# OPA541.net
KiCad netlist of a schematic drawn in EasyEDA Pro
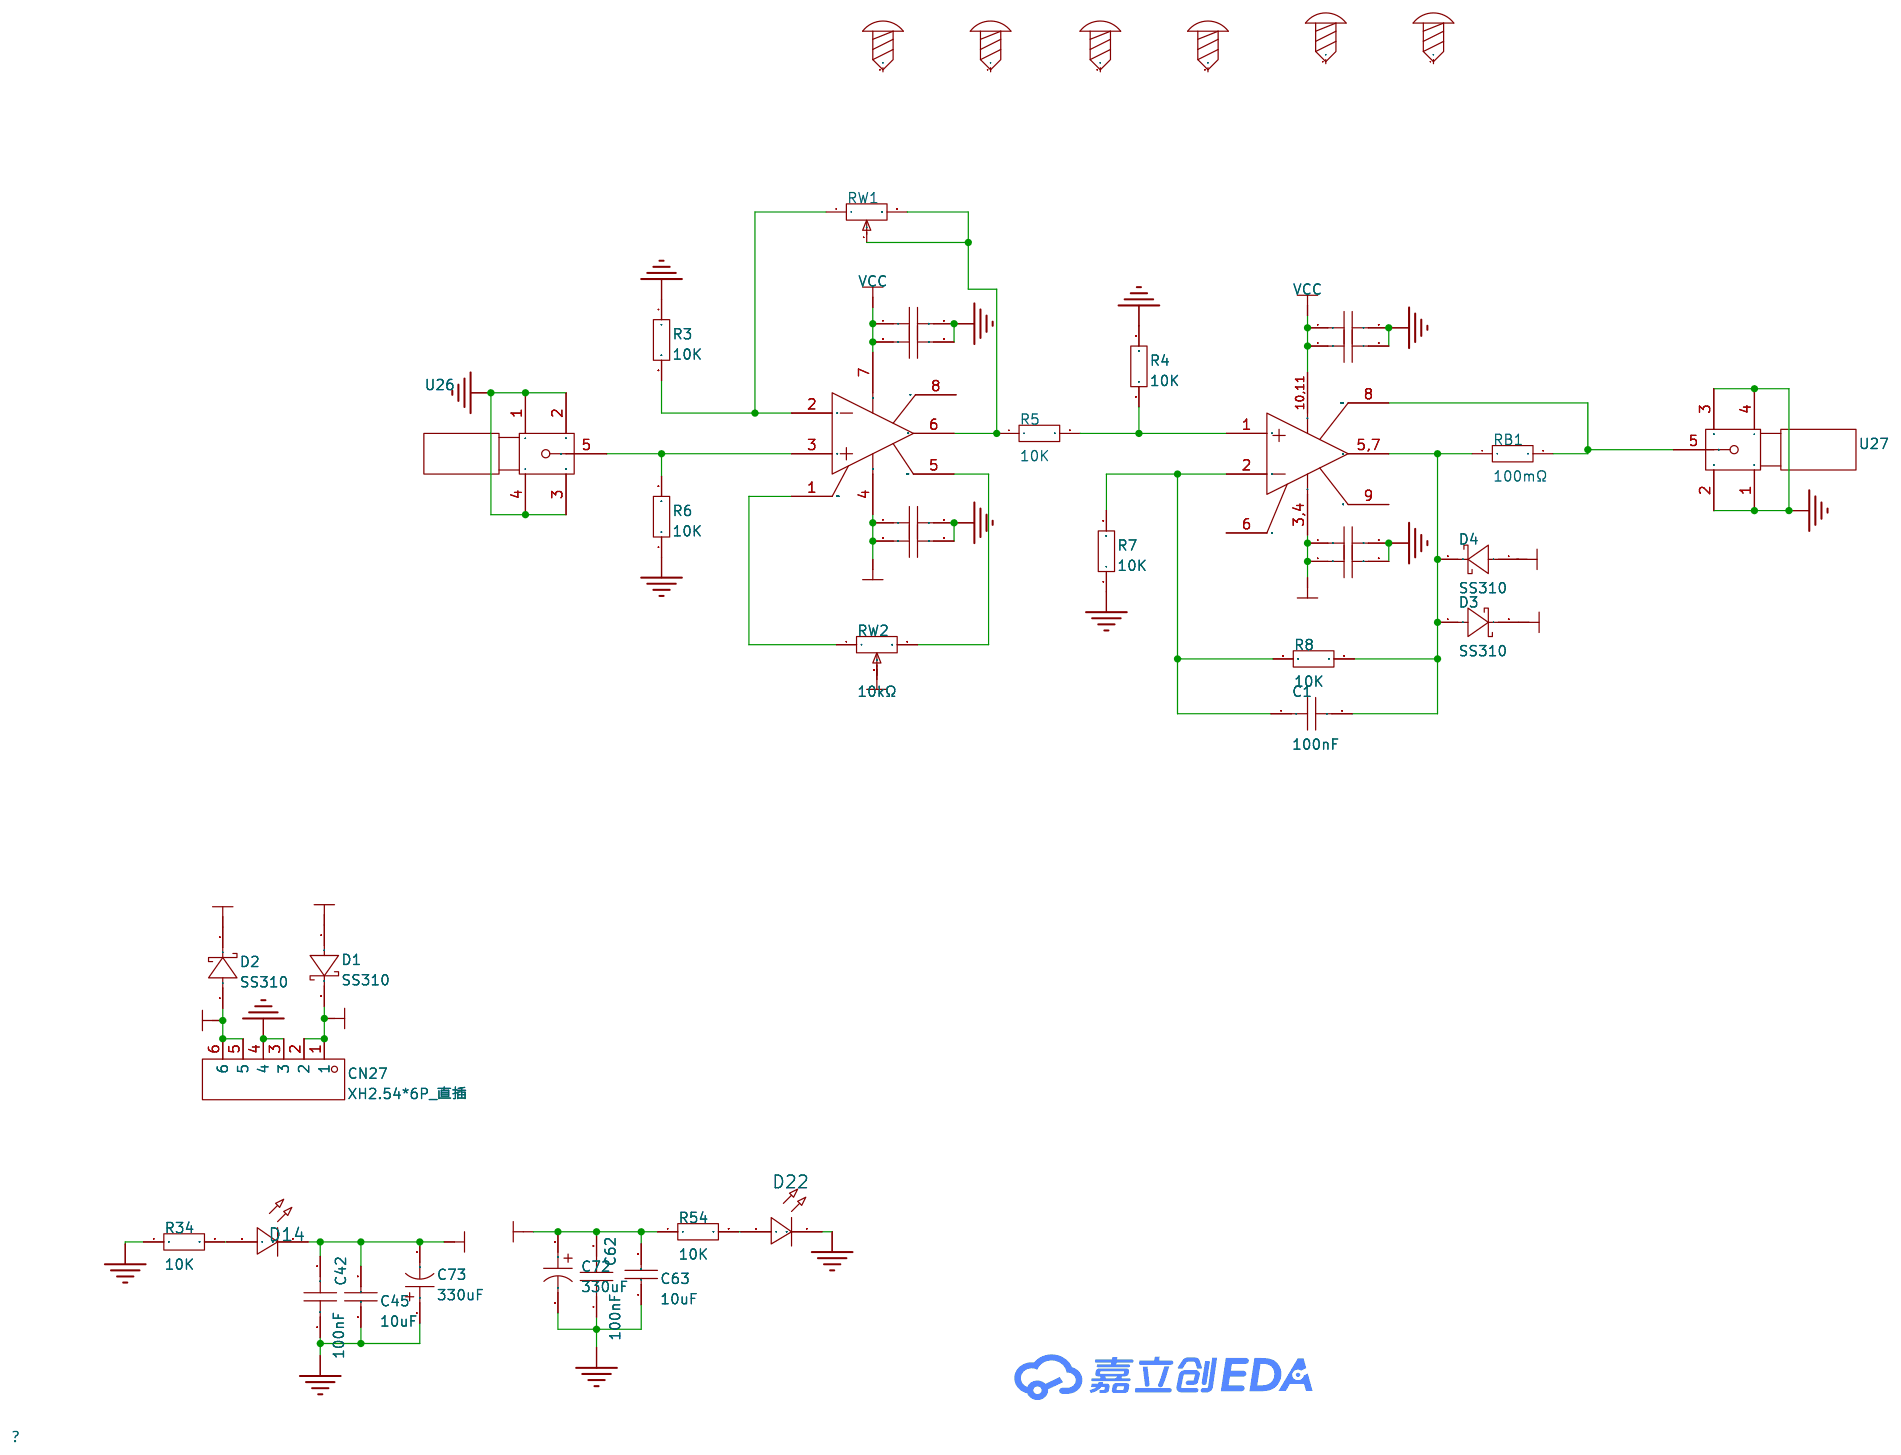
[diagram p0: schematic sheet]

(export (version "E")
  (design (tool "Eeschema 10.0.6"))
  (components
    (comp (ref "C1")
      (value "100nF")
      (footprint "easyedapro:C0805")
      (libsource (lib "easyedapro") (part "CapAcitance"))
    )
    (comp (ref "C42")
      (value "100nF")
      (footprint "easyedapro:C0805")
      (libsource (lib "easyedapro") (part "CapAcitance"))
    )
    (comp (ref "C45")
      (value "10uF")
      (footprint "easyedapro:C1210")
      (description "容值:10uF;精度:±10%;额定电压:25V;材质(温度系数):X7R;")
      (fields
        (field (name "Manufacturer Part") "CL32B106KAJNNNE")
        (field (name "Manufacturer") "SAMSUNG(三星)")
      )
      (libsource (lib "easyedapro") (part "CL32B106KAJNNNE"))
    )
    (comp (ref "C62")
      (value "100nF")
      (footprint "easyedapro:C0805")
      (libsource (lib "easyedapro") (part "CapAcitance"))
    )
    (comp (ref "C63")
      (value "10uF")
      (footprint "easyedapro:C1210")
      (description "容值:10uF;精度:±10%;额定电压:25V;材质(温度系数):X7R;")
      (fields
        (field (name "Manufacturer Part") "CL32B106KAJNNNE")
        (field (name "Manufacturer") "SAMSUNG(三星)")
      )
      (libsource (lib "easyedapro") (part "CL32B106KAJNNNE"))
    )
    (comp (ref "C64")
      (value "100nF")
      (footprint "easyedapro:C0805")
      (libsource (lib "easyedapro") (part "CapAcitance"))
    )
    (comp (ref "C65")
      (value "100nF")
      (footprint "easyedapro:C0805")
      (libsource (lib "easyedapro") (part "CapAcitance"))
    )
    (comp (ref "C66")
      (value "100nF")
      (footprint "easyedapro:C0805")
      (libsource (lib "easyedapro") (part "CapAcitance"))
    )
    (comp (ref "C67")
      (value "100nF")
      (footprint "easyedapro:C0805")
      (libsource (lib "easyedapro") (part "CapAcitance"))
    )
    (comp (ref "C68")
      (value "100nF")
      (footprint "easyedapro:C0805")
      (libsource (lib "easyedapro") (part "CapAcitance"))
    )
    (comp (ref "C69")
      (value "100nF")
      (footprint "easyedapro:C0805")
      (libsource (lib "easyedapro") (part "CapAcitance"))
    )
    (comp (ref "C70")
      (value "100nF")
      (footprint "easyedapro:C0805")
      (libsource (lib "easyedapro") (part "CapAcitance"))
    )
    (comp (ref "C71")
      (value "100nF")
      (footprint "easyedapro:C0805")
      (libsource (lib "easyedapro") (part "CapAcitance"))
    )
    (comp (ref "C72")
      (value "330uF")
      (footprint "easyedapro:CAP-SMD_BD10.0-L10.3-W10.3-LS11.0-FD-1")
      (description "容值:330uF;精度:±20%;额定电压:50V;纹波电流:285mA@120Hz;")
      (fields (field (name "Manufacturer Part") "CS1H331M-CRG10") (field (name "Manufacturer") "ROQANG(容强)"))
      (libsource (lib "easyedapro") (part "CS1H331M-CRG10"))
    )
    (comp (ref "C73")
      (value "330uF")
      (footprint "easyedapro:CAP-SMD_BD10.0-L10.3-W10.3-LS11.0-FD-1")
      (description "容值:330uF;精度:±20%;额定电压:50V;纹波电流:285mA@120Hz;")
      (fields (field (name "Manufacturer Part") "CS1H331M-CRG10") (field (name "Manufacturer") "ROQANG(容强)"))
      (libsource (lib "easyedapro") (part "CS1H331M-CRG10"))
    )
    (comp (ref "CN27")
      (value "XH2.54*6P_直插")
      (footprint "easyedapro:CONN-TH_XH2.54-6P")
      (libsource (lib "easyedapro") (part "XH2.54*6P_直插"))
    )
    (comp (ref "D1")
      (value "SS310")
      (footprint "easyedapro:SMA_L4.3-W2.6-LS5.0-FD")
      (description "二极管配置:独立式;正向压降(Vf):850mV@3A;直流反向耐压(Vr):100V;整流电流:3A;")
      (fields (field (name "Manufacturer") "宏迦橙"))
      (libsource (lib "easyedapro") (part "SS310_C7420364"))
    )
    (comp (ref "D2")
      (value "SS310")
      (footprint "easyedapro:SMA_L4.3-W2.6-LS5.0-FD")
      (description "二极管配置:独立式;正向压降(Vf):850mV@3A;直流反向耐压(Vr):100V;整流电流:3A;")
      (fields (field (name "Manufacturer") "宏迦橙"))
      (libsource (lib "easyedapro") (part "SS310_C7420364"))
    )
    (comp (ref "D3")
      (value "SS310")
      (footprint "easyedapro:SMA_L4.3-W2.6-LS5.0-FD")
      (description "二极管配置:独立式;正向压降(Vf):850mV@3A;直流反向耐压(Vr):100V;整流电流:3A;")
      (fields (field (name "Manufacturer") "宏迦橙"))
      (libsource (lib "easyedapro") (part "SS310_C7420364"))
    )
    (comp (ref "D4")
      (value "SS310")
      (footprint "easyedapro:SMA_L4.3-W2.6-LS5.0-FD")
      (description "二极管配置:独立式;正向压降(Vf):850mV@3A;直流反向耐压(Vr):100V;整流电流:3A;")
      (fields (field (name "Manufacturer") "宏迦橙"))
      (libsource (lib "easyedapro") (part "SS310_C7420364"))
    )
    (comp (ref "D14")
      (value "~")
      (footprint "easyedapro:LED_0805")
      (libsource (lib "easyedapro") (part "LED_R"))
    )
    (comp (ref "D22")
      (value "~")
      (footprint "easyedapro:LED_0805")
      (libsource (lib "easyedapro") (part "LED_R"))
    )
    (comp (ref "R3") (value "10K") (footprint "easyedapro:R0805") (libsource (lib "easyedapro") (part "电阻")))
    (comp (ref "R4") (value "10K") (footprint "easyedapro:R0805") (libsource (lib "easyedapro") (part "电阻")))
    (comp (ref "R5") (value "10K") (footprint "easyedapro:R0805") (libsource (lib "easyedapro") (part "电阻")))
    (comp (ref "R6") (value "10K") (footprint "easyedapro:R0805") (libsource (lib "easyedapro") (part "电阻")))
    (comp (ref "R7") (value "10K") (footprint "easyedapro:R0805") (libsource (lib "easyedapro") (part "电阻")))
    (comp (ref "R8") (value "10K") (footprint "easyedapro:R0805") (libsource (lib "easyedapro") (part "电阻")))
    (comp (ref "R34") (value "10K") (footprint "easyedapro:R0805") (libsource (lib "easyedapro") (part "电阻")))
    (comp (ref "R54") (value "10K") (footprint "easyedapro:R0805") (libsource (lib "easyedapro") (part "电阻")))
    (comp (ref "RB1")
      (value "100mΩ")
      (footprint "easyedapro:RES-TH_L13.0-W9.5-P4.50-D0.7")
      (description "电阻类型:水泥电阻;阻值:100mΩ;精度:±5%;功率:5W;温度系数:-1500ppm/°C~+300ppm/°C;")
      (fields (field (name "Manufacturer Part") "CR-M5W-0.1ΩJ") (field (name "Manufacturer") "华星机电"))
      (libsource (lib "easyedapro") (part "CR-M5W-0.1ΩJ_C714791"))
    )
    (comp (ref "RW1")
      (value "10kΩ")
      (footprint "easyedapro:R_3296")
      (libsource (lib "easyedapro") (part "R_3296"))
    )
    (comp (ref "RW2")
      (value "10kΩ")
      (footprint "easyedapro:R_3296")
      (libsource (lib "easyedapro") (part "R_3296"))
    )
    (comp (ref "SCREW1")
      (value "~")
      (footprint "easyedapro:M3螺丝")
      (libsource (lib "easyedapro") (part "螺丝孔"))
    )
    (comp (ref "SCREW2")
      (value "~")
      (footprint "easyedapro:M3螺丝")
      (libsource (lib "easyedapro") (part "螺丝孔"))
    )
    (comp (ref "SCREW3")
      (value "~")
      (footprint "easyedapro:M3螺丝")
      (libsource (lib "easyedapro") (part "螺丝孔"))
    )
    (comp (ref "SCREW4")
      (value "~")
      (footprint "easyedapro:M3螺丝")
      (libsource (lib "easyedapro") (part "螺丝孔"))
    )
    (comp (ref "SCREW5")
      (value "~")
      (footprint "easyedapro:M3螺丝")
      (libsource (lib "easyedapro") (part "螺丝孔"))
    )
    (comp (ref "SCREW6")
      (value "~")
      (footprint "easyedapro:M3螺丝")
      (libsource (lib "easyedapro") (part "螺丝孔"))
    )
    (comp (ref "U1")
      (value "OPA541AP")
      (footprint "easyedapro:TO-220-11_L20.0-W4.5-P1.70-BL")
      (description "放大器数:单路;增益带宽积(GBP):1.6MHz;输入偏置电流(Ib):4pA;压摆率(SR):10V/us;轨到轨:-;")
      (fields (field (name "Manufacturer") "TI(德州仪器)"))
      (libsource (lib "easyedapro") (part "OPA541AP"))
    )
    (comp (ref "U2")
      (value "OPA445AU/2K5")
      (footprint "easyedapro:SOIC-8_L4.9-W3.9-P1.27-LS6.0-BL")
      (description "OPA445 高电压 FET 输入运算放大器")
      (fields (field (name "Manufacturer") "TI(德州仪器)"))
      (libsource (lib "easyedapro") (part "OPA445"))
    )
    (comp (ref "U26") (value "~") (footprint "easyedapro:SMA") (libsource (lib "easyedapro") (part "SMA")))
    (comp (ref "U27") (value "~") (footprint "easyedapro:SMA") (libsource (lib "easyedapro") (part "SMA")))
  )
  (nets
    (net (code "1") (name "GND") (class "Default")
      (node (ref "C42") (pin "1") (pinfunction "1_1") (pintype "input"))
      (node (ref "C45") (pin "1") (pinfunction "1_1") (pintype "input"))
      (node (ref "C62") (pin "1") (pinfunction "1_1") (pintype "input"))
      (node (ref "C63") (pin "1") (pinfunction "1_1") (pintype "input"))
      (node (ref "C64") (pin "2") (pinfunction "2_2") (pintype "input"))
      (node (ref "C65") (pin "2") (pinfunction "2_2") (pintype "input"))
      (node (ref "C66") (pin "2") (pinfunction "2_2") (pintype "input"))
      (node (ref "C67") (pin "2") (pinfunction "2_2") (pintype "input"))
      (node (ref "C68") (pin "2") (pinfunction "2_2") (pintype "input"))
      (node (ref "C69") (pin "2") (pinfunction "2_2") (pintype "input"))
      (node (ref "C70") (pin "2") (pinfunction "2_2") (pintype "input"))
      (node (ref "C71") (pin "2") (pinfunction "2_2") (pintype "input"))
      (node (ref "C72") (pin "2") (pinfunction "2_2") (pintype "input"))
      (node (ref "C73") (pin "1") (pinfunction "1_1") (pintype "input"))
      (node (ref "CN27") (pin "3") (pinfunction "3_3") (pintype "unspecified"))
      (node (ref "CN27") (pin "4") (pinfunction "4_4") (pintype "unspecified"))
      (node (ref "D22") (pin "1") (pinfunction "C_1") (pintype "input"))
      (node (ref "R3") (pin "1") (pinfunction "1_1") (pintype "input"))
      (node (ref "R34") (pin "1") (pinfunction "1_1") (pintype "input"))
      (node (ref "R4") (pin "2") (pinfunction "2_2") (pintype "input"))
      (node (ref "R6") (pin "1") (pinfunction "1_1") (pintype "input"))
      (node (ref "R7") (pin "1") (pinfunction "1_1") (pintype "input"))
      (node (ref "U26") (pin "1") (pinfunction "1_1") (pintype "input"))
      (node (ref "U26") (pin "2") (pinfunction "2_2") (pintype "input"))
      (node (ref "U26") (pin "3") (pinfunction "3_3") (pintype "input"))
      (node (ref "U26") (pin "4") (pinfunction "4_4") (pintype "input"))
      (node (ref "U27") (pin "1") (pinfunction "1_1") (pintype "input"))
      (node (ref "U27") (pin "2") (pinfunction "2_2") (pintype "input"))
      (node (ref "U27") (pin "3") (pinfunction "3_3") (pintype "input"))
      (node (ref "U27") (pin "4") (pinfunction "4_4") (pintype "input"))
    )
    (net (code "2") (name "Net-(C1-Pad1)") (class "Default")
      (node (ref "C1") (pin "1") (pinfunction "1_1") (pintype "input"))
      (node (ref "R7") (pin "2") (pinfunction "2_2") (pintype "input"))
      (node (ref "R8") (pin "2") (pinfunction "2_2") (pintype "input"))
      (node (ref "U1") (pin "2") (pinfunction "IN+_2") (pintype "unspecified"))
    )
    (net (code "3") (name "Net-(D3-A)") (class "Default")
      (node (ref "C1") (pin "2") (pinfunction "2_2") (pintype "input"))
      (node (ref "D3") (pin "1") (pinfunction "A_1") (pintype "unspecified"))
      (node (ref "D4") (pin "2") (pinfunction "K_2") (pintype "unspecified"))
      (node (ref "R8") (pin "1") (pinfunction "1_1") (pintype "input"))
      (node (ref "RB1") (pin "1") (pinfunction "1_1") (pintype "unspecified"))
      (node (ref "U1") (pin "5,7") (pinfunction "OUT_5,7") (pintype "output"))
    )
    (net (code "4") (name "Net-(D14-A)") (class "Default")
      (node (ref "D14") (pin "2") (pinfunction "A_2") (pintype "input"))
      (node (ref "R34") (pin "2") (pinfunction "2_2") (pintype "input"))
    )
    (net (code "5") (name "Net-(D22-A)") (class "Default")
      (node (ref "D22") (pin "2") (pinfunction "A_2") (pintype "input"))
      (node (ref "R54") (pin "2") (pinfunction "2_2") (pintype "input"))
    )
    (net (code "6") (name "Net-(R4-Pad1)") (class "Default")
      (node (ref "R4") (pin "1") (pinfunction "1_1") (pintype "input"))
      (node (ref "R5") (pin "2") (pinfunction "2_2") (pintype "input"))
      (node (ref "U1") (pin "1") (pinfunction "IN+_1") (pintype "unspecified"))
    )
    (net (code "7") (name "Net-(RW2-Pad1)") (class "Default")
      (node (ref "RW2") (pin "1") (pinfunction "1_1") (pintype "input"))
      (node (ref "U2") (pin "1") (pinfunction "Offset_Trim_1") (pintype "unspecified"))
    )
    (net (code "8") (name "Net-(RW2-Pad3)") (class "Default")
      (node (ref "RW2") (pin "3") (pinfunction "3_3") (pintype "input"))
      (node (ref "U2") (pin "5") (pinfunction "Offset_Trim_5") (pintype "unspecified"))
    )
    (net (code "9") (name "Net-(U1-Curent_Sence)") (class "Default")
      (node (ref "RB1") (pin "2") (pinfunction "2_2") (pintype "unspecified"))
      (node (ref "U1") (pin "8") (pinfunction "Curent_Sence_8") (pintype "unspecified"))
      (node (ref "U27") (pin "5") (pinfunction "5_5") (pintype "input"))
    )
    (net (code "10") (name "Net-(U2-IN+)") (class "Default")
      (node (ref "R6") (pin "2") (pinfunction "2_2") (pintype "input"))
      (node (ref "U2") (pin "3") (pinfunction "IN+_3") (pintype "unspecified"))
      (node (ref "U26") (pin "5") (pinfunction "5_5") (pintype "input"))
    )
    (net (code "11") (name "Net-(U2-IN-)") (class "Default")
      (node (ref "R3") (pin "2") (pinfunction "2_2") (pintype "input"))
      (node (ref "RW1") (pin "1") (pinfunction "1_1") (pintype "input"))
      (node (ref "U2") (pin "2") (pinfunction "IN-_2") (pintype "unspecified"))
    )
    (net (code "12") (name "Net-(U2-OUT)") (class "Default")
      (node (ref "R5") (pin "1") (pinfunction "1_1") (pintype "input"))
      (node (ref "RW1") (pin "2") (pinfunction "2_2") (pintype "input"))
      (node (ref "RW1") (pin "3") (pinfunction "3_3") (pintype "input"))
      (node (ref "U2") (pin "6") (pinfunction "OUT_6") (pintype "output"))
    )
    (net (code "13") (name "VCC") (class "Default")
      (node (ref "C62") (pin "2") (pinfunction "2_2") (pintype "input"))
      (node (ref "C63") (pin "2") (pinfunction "2_2") (pintype "input"))
      (node (ref "C64") (pin "1") (pinfunction "1_1") (pintype "input"))
      (node (ref "C65") (pin "1") (pinfunction "1_1") (pintype "input"))
      (node (ref "C68") (pin "1") (pinfunction "1_1") (pintype "input"))
      (node (ref "C69") (pin "1") (pinfunction "1_1") (pintype "input"))
      (node (ref "C72") (pin "1") (pinfunction "1_1") (pintype "input"))
      (node (ref "D2") (pin "2") (pinfunction "K_2") (pintype "unspecified"))
      (node (ref "R54") (pin "1") (pinfunction "1_1") (pintype "input"))
      (node (ref "U1") (pin "10,11") (pinfunction "V+_10,11") (pintype "unspecified"))
      (node (ref "U2") (pin "7") (pinfunction "VCC+_7") (pintype "unspecified"))
    )
    (net (code "14") (name "VCCI") (class "Default")
      (node (ref "CN27") (pin "5") (pinfunction "5_5") (pintype "unspecified"))
      (node (ref "CN27") (pin "6") (pinfunction "6_6") (pintype "unspecified"))
      (node (ref "D2") (pin "1") (pinfunction "A_1") (pintype "unspecified"))
      (node (ref "D3") (pin "2") (pinfunction "K_2") (pintype "unspecified"))
    )
    (net (code "15") (name "VDD") (class "Default")
      (node (ref "C42") (pin "2") (pinfunction "2_2") (pintype "input"))
      (node (ref "C45") (pin "2") (pinfunction "2_2") (pintype "input"))
      (node (ref "C66") (pin "1") (pinfunction "1_1") (pintype "input"))
      (node (ref "C67") (pin "1") (pinfunction "1_1") (pintype "input"))
      (node (ref "C70") (pin "1") (pinfunction "1_1") (pintype "input"))
      (node (ref "C71") (pin "1") (pinfunction "1_1") (pintype "input"))
      (node (ref "C73") (pin "2") (pinfunction "2_2") (pintype "input"))
      (node (ref "D1") (pin "1") (pinfunction "A_1") (pintype "unspecified"))
      (node (ref "D14") (pin "1") (pinfunction "C_1") (pintype "input"))
      (node (ref "RW2") (pin "2") (pinfunction "2_2") (pintype "input"))
      (node (ref "U1") (pin "3,4") (pinfunction "V-_3,4") (pintype "unspecified"))
      (node (ref "U2") (pin "4") (pinfunction "VCC-_4") (pintype "unspecified"))
    )
    (net (code "16") (name "VDDI") (class "Default")
      (node (ref "CN27") (pin "1") (pinfunction "1_1") (pintype "unspecified"))
      (node (ref "CN27") (pin "2") (pinfunction "2_2") (pintype "unspecified"))
      (node (ref "D1") (pin "2") (pinfunction "K_2") (pintype "unspecified"))
      (node (ref "D4") (pin "1") (pinfunction "A_1") (pintype "unspecified"))
    )
    (net (code "17") (name "unconnected-(SCREW1-Pad1)") (class "Default")
      (node (ref "SCREW1") (pin "1") (pinfunction "1_1") (pintype "input"))
    )
    (net (code "18") (name "unconnected-(SCREW2-Pad1)") (class "Default")
      (node (ref "SCREW2") (pin "1") (pinfunction "1_1") (pintype "input"))
    )
    (net (code "19") (name "unconnected-(SCREW3-Pad1)") (class "Default")
      (node (ref "SCREW3") (pin "1") (pinfunction "1_1") (pintype "input"))
    )
    (net (code "20") (name "unconnected-(SCREW4-Pad1)") (class "Default")
      (node (ref "SCREW4") (pin "1") (pinfunction "1_1") (pintype "input"))
    )
    (net (code "21") (name "unconnected-(SCREW5-Pad1)") (class "Default")
      (node (ref "SCREW5") (pin "1") (pinfunction "1_1") (pintype "input"))
    )
    (net (code "22") (name "unconnected-(SCREW6-Pad1)") (class "Default")
      (node (ref "SCREW6") (pin "1") (pinfunction "1_1") (pintype "input"))
    )
    (net (code "23") (name "unconnected-(U1-NC-Pad6)") (class "Default")
      (node (ref "U1") (pin "6") (pinfunction "NC_6") (pintype "unspecified"))
    )
    (net (code "24") (name "unconnected-(U1-Pad9)") (class "Default")
      (node (ref "U1") (pin "9") (pinfunction "9_9") (pintype "unspecified"))
    )
    (net (code "25") (name "unconnected-(U2-NC-Pad8)") (class "Default")
      (node (ref "U2") (pin "8") (pinfunction "NC_8") (pintype "unspecified"))
    )
  )
)
